# LoadCellAmp2.net
KiCad netlist of a schematic drawn in Altium Designer
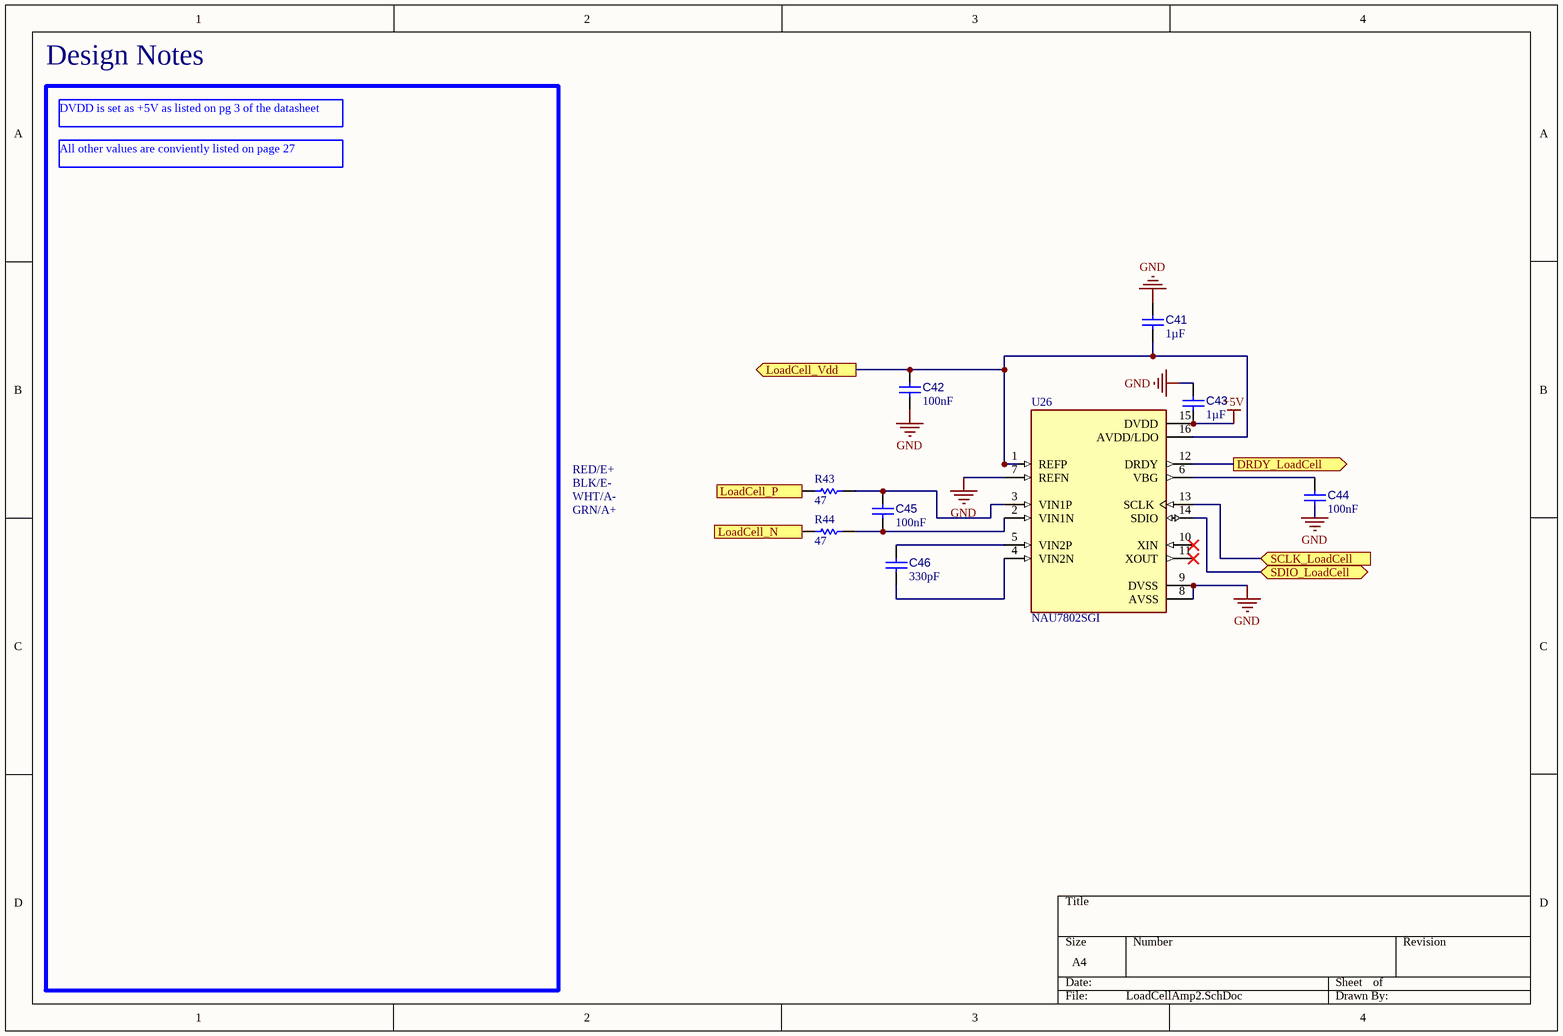
[diagram p0: LoadCellAmp2.SchDoc]

(export (version "E")
  (design (tool "Eeschema 10.0.6"))
  (components
    (comp (ref "C41")
      (value "1µF")
      (footprint "CAPC2013X135X45ML10T25")
      (description "Chip Capacitor, 1 uF, +/- 10%, 50 V, 0805 (2012 Metric)")
      (fields (field (name "TOLERANCE") "10%") (field (name "Comment") "Capacitor 1 uF +/- 10% 50 V 0805"))
      (libsource (lib "University of Calgary - SOAR") (part "CAP-NP-2"))
    )
    (comp (ref "C42")
      (value "100nF")
      (footprint "CAPC1608X90X40NL10T20")
      (description "Chip Capacitor, 100 nF, +/- 10%, 50 V, 0603 (1608 Metric)")
      (fields (field (name "TOLERANCE") "10%") (field (name "Comment") "Capacitor 100 nF +/-10% 50 V 0603"))
      (libsource (lib "University of Calgary - SOAR") (part "CAP-NP-2"))
    )
    (comp (ref "C43")
      (value "1µF")
      (footprint "CAPC2013X135X45ML10T25")
      (description "Chip Capacitor, 1 uF, +/- 10%, 50 V, 0805 (2012 Metric)")
      (fields (field (name "TOLERANCE") "10%") (field (name "Comment") "Capacitor 1 uF +/- 10% 50 V 0805"))
      (libsource (lib "University of Calgary - SOAR") (part "CAP-NP-2"))
    )
    (comp (ref "C44")
      (value "100nF")
      (footprint "CAPC1608X90X40NL10T20")
      (description "Chip Capacitor, 100 nF, +/- 10%, 50 V, 0603 (1608 Metric)")
      (fields (field (name "TOLERANCE") "10%") (field (name "Comment") "Capacitor 100 nF +/-10% 50 V 0603"))
      (libsource (lib "University of Calgary - SOAR") (part "CAP-NP-2"))
    )
    (comp (ref "C45")
      (value "100nF")
      (footprint "CAPC1608X90X40NL10T20")
      (description "Chip Capacitor, 100 nF, +/- 10%, 50 V, 0603 (1608 Metric)")
      (fields (field (name "TOLERANCE") "10%") (field (name "Comment") "Capacitor 100 nF +/-10% 50 V 0603"))
      (libsource (lib "University of Calgary - SOAR") (part "CAP-NP-2"))
    )
    (comp (ref "C46")
      (value "330pF")
      (footprint "CAP_0603")
      (description "KGM15ACG1H331FT - Cap Ceramic 330pF 50V C0G 1% Pad SMD 0603 125C T/R")
      (fields (field (name "Comment") "CAP CER 330pF 50V 1% 0603"))
      (libsource (lib "University of Calgary - SOAR") (part "CAP-NP-2"))
    )
    (comp (ref "R43")
      (value "47")
      (footprint "RESC1608X50X30ML20T20")
      (description "Fixed Resistor, Metal Film, 0.1W, 47ohm, 75V, 0.05% +/-Tol, 10ppm/Cel, Surface Mount, 0603")
      (fields (field (name "TOLERANCE") "0.05%") (field (name "POWER") "100mW"))
      (libsource (lib "University of Calgary - SOAR") (part "RES"))
    )
    (comp (ref "R44")
      (value "47")
      (footprint "RESC1608X50X30ML20T20")
      (description "Fixed Resistor, Metal Film, 0.1W, 47ohm, 75V, 0.05% +/-Tol, 10ppm/Cel, Surface Mount, 0603")
      (fields (field (name "TOLERANCE") "0.05%") (field (name "POWER") "100mW"))
      (libsource (lib "University of Calgary - SOAR") (part "RES"))
    )
    (comp (ref "U26")
      (value "NAU7802SGI")
      (footprint "NAU7802SGI-Footprint-1")
      (description "ADC, Delta-Sigma, 24-Bit, 1 Func, 2 Channel, Serial Access, PDSO16")
      (libsource (lib "University of Calgary - SOAR") (part "AMP-3"))
    )
  )
  (nets
    (net (code "1") (name "+5V") (class "Default")
      (node (ref "C43") (pin "1") (pinfunction "1_1") (pintype "passive"))
      (node (ref "U26") (pin "15") (pinfunction "DVDD_15") (pintype "power_in"))
    )
    (net (code "2") (name "/DRDY_LoadCell") (class "Default")
      (node (ref "U26") (pin "12") (pinfunction "DRDY_12") (pintype "output"))
    )
    (net (code "3") (name "/LoadCell_N") (class "Default")
      (node (ref "R44") (pin "1") (pinfunction "1_1") (pintype "passive"))
    )
    (net (code "4") (name "/LoadCell_P") (class "Default")
      (node (ref "R43") (pin "1") (pinfunction "1_1") (pintype "passive"))
    )
    (net (code "5") (name "/LoadCell_Vdd") (class "Default")
      (node (ref "C41") (pin "1") (pinfunction "1_1") (pintype "passive"))
      (node (ref "C42") (pin "2") (pinfunction "2_2") (pintype "passive"))
      (node (ref "U26") (pin "1") (pinfunction "REFP_1") (pintype "input"))
      (node (ref "U26") (pin "16") (pinfunction "AVDD/LDO_16") (pintype "power_in"))
    )
    (net (code "6") (name "/SCLK_LoadCell") (class "Default")
      (node (ref "U26") (pin "13") (pinfunction "SCLK_13") (pintype "input"))
    )
    (net (code "7") (name "/SDIO_LoadCell") (class "Default")
      (node (ref "U26") (pin "14") (pinfunction "SDIO_14") (pintype "bidirectional"))
    )
    (net (code "8") (name "GND") (class "Default")
      (node (ref "C41") (pin "2") (pinfunction "2_2") (pintype "passive"))
      (node (ref "C42") (pin "1") (pinfunction "1_1") (pintype "passive"))
      (node (ref "C43") (pin "2") (pinfunction "2_2") (pintype "passive"))
      (node (ref "C44") (pin "1") (pinfunction "1_1") (pintype "passive"))
      (node (ref "U26") (pin "7") (pinfunction "REFN_7") (pintype "input"))
      (node (ref "U26") (pin "8") (pinfunction "AVSS_8") (pintype "power_in"))
      (node (ref "U26") (pin "9") (pinfunction "DVSS_9") (pintype "power_in"))
    )
    (net (code "9") (name "Net-(U26-VBG)") (class "Default")
      (node (ref "C44") (pin "2") (pinfunction "2_2") (pintype "passive"))
      (node (ref "U26") (pin "6") (pinfunction "VBG_6") (pintype "output"))
    )
    (net (code "10") (name "Net-(U26-VIN1N)") (class "Default")
      (node (ref "C45") (pin "1") (pinfunction "1_1") (pintype "passive"))
      (node (ref "R44") (pin "2") (pinfunction "2_2") (pintype "passive"))
      (node (ref "U26") (pin "2") (pinfunction "VIN1N_2") (pintype "input"))
    )
    (net (code "11") (name "Net-(U26-VIN1P)") (class "Default")
      (node (ref "C45") (pin "2") (pinfunction "2_2") (pintype "passive"))
      (node (ref "R43") (pin "2") (pinfunction "2_2") (pintype "passive"))
      (node (ref "U26") (pin "3") (pinfunction "VIN1P_3") (pintype "input"))
    )
    (net (code "12") (name "Net-(U26-VIN2N)") (class "Default")
      (node (ref "C46") (pin "1") (pinfunction "1_1") (pintype "passive"))
      (node (ref "U26") (pin "4") (pinfunction "VIN2N_4") (pintype "input"))
    )
    (net (code "13") (name "Net-(U26-VIN2P)") (class "Default")
      (node (ref "C46") (pin "2") (pinfunction "2_2") (pintype "passive"))
      (node (ref "U26") (pin "5") (pinfunction "VIN2P_5") (pintype "input"))
    )
    (net (code "14") (name "unconnected-(U26-XIN-Pad10)") (class "Default")
      (node (ref "U26") (pin "10") (pinfunction "XIN_10") (pintype "input+no_connect"))
    )
    (net (code "15") (name "unconnected-(U26-XOUT-Pad11)") (class "Default")
      (node (ref "U26") (pin "11") (pinfunction "XOUT_11") (pintype "output+no_connect"))
    )
  )
)
